# relayboard.net
KiCad netlist of a schematic drawn in EAGLE
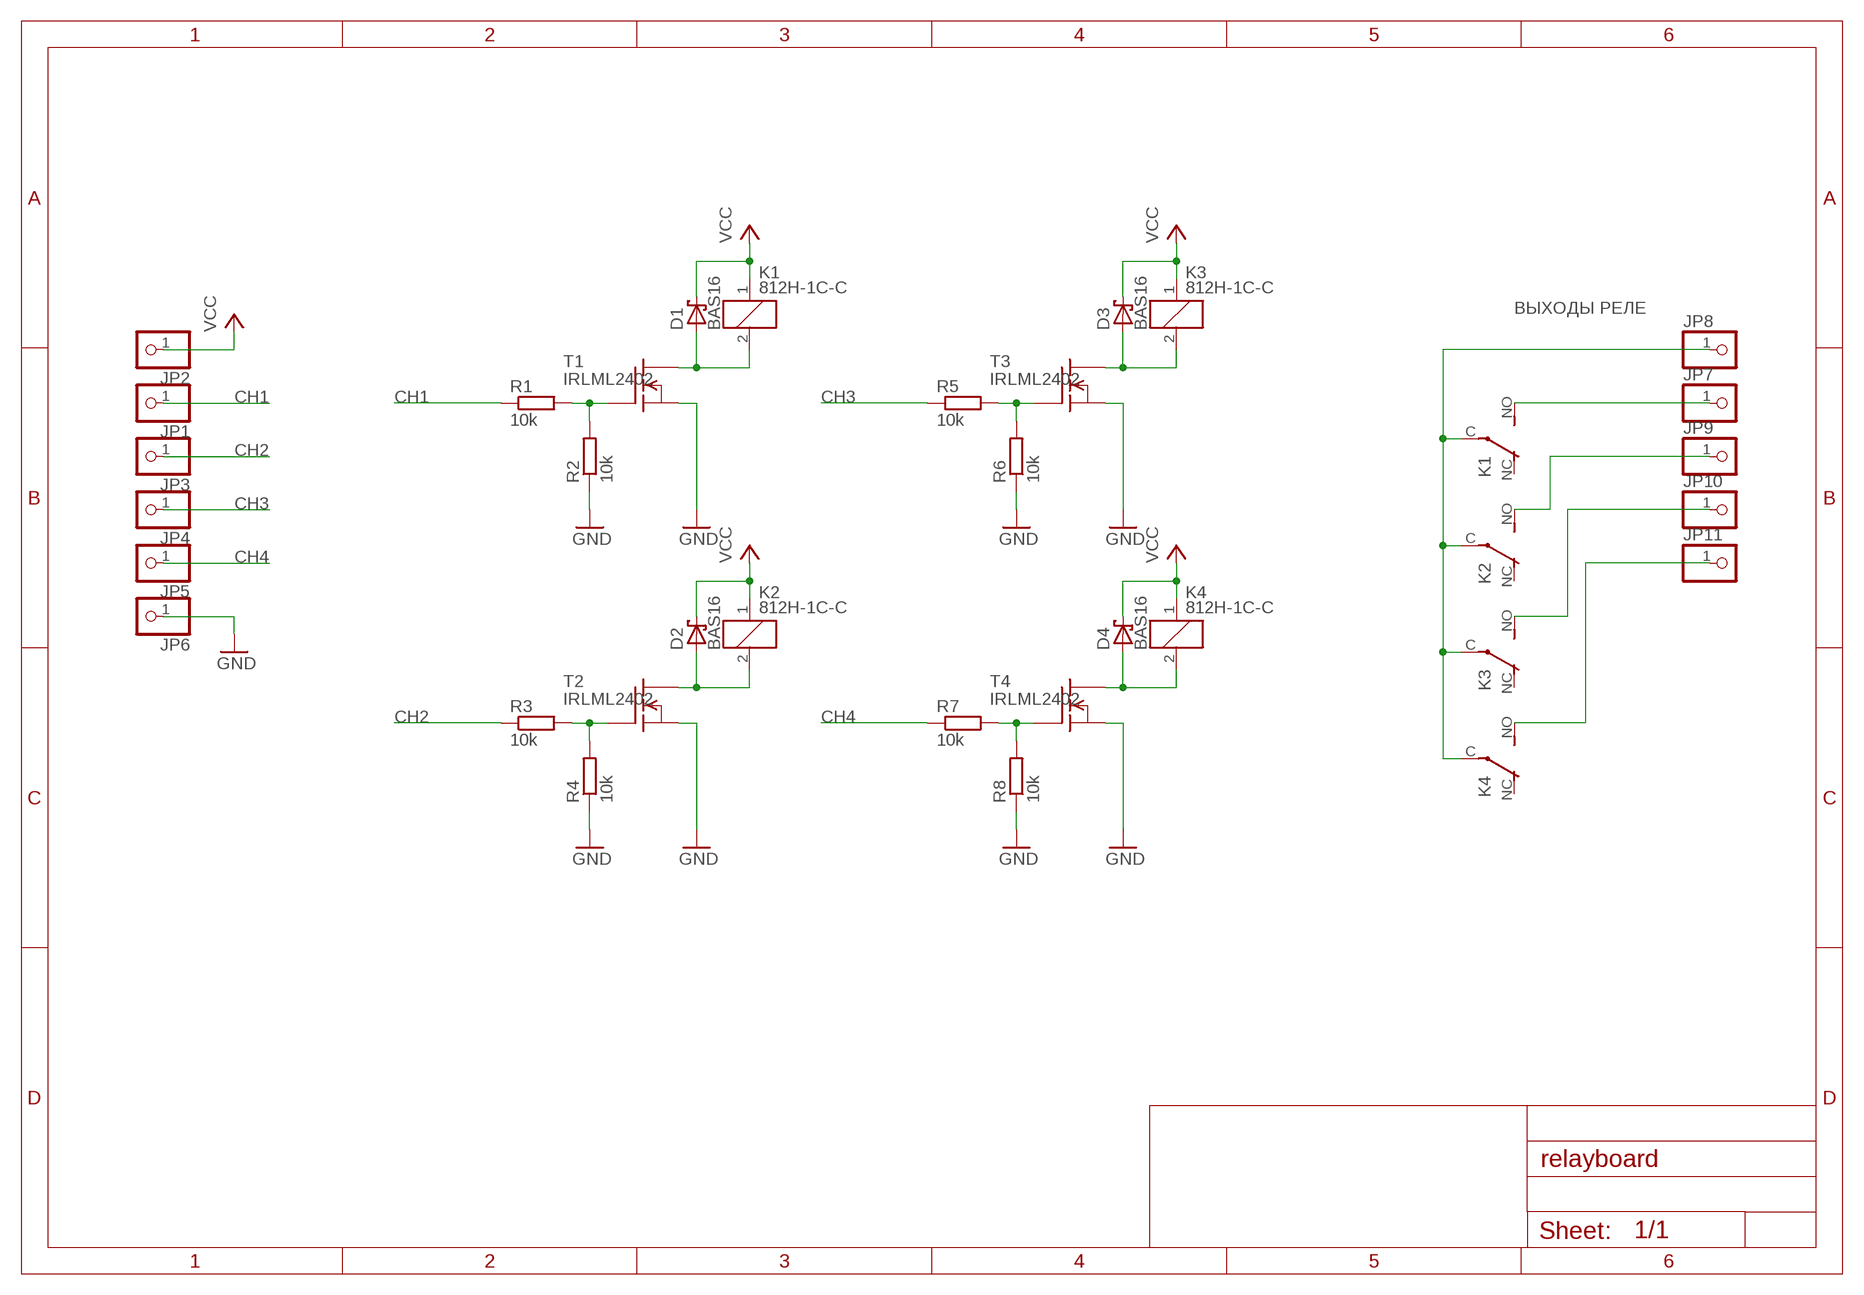
[diagram p0: schematic, sheet 1]

(export (version "E")
  (design (tool "Eeschema 10.0.6"))
  (components
    (comp (ref "D1")
      (value "BAS16")
      (footprint "eagle-import:SOT23")
      (libsource (lib "eagle-import") (part "BAS16"))
    )
    (comp (ref "D2")
      (value "BAS16")
      (footprint "eagle-import:SOT23")
      (libsource (lib "eagle-import") (part "BAS16"))
    )
    (comp (ref "D3")
      (value "BAS16")
      (footprint "eagle-import:SOT23")
      (libsource (lib "eagle-import") (part "BAS16"))
    )
    (comp (ref "D4")
      (value "BAS16")
      (footprint "eagle-import:SOT23")
      (libsource (lib "eagle-import") (part "BAS16"))
    )
    (comp (ref "JP1")
      (value "PINHD-1X1")
      (footprint "eagle-import:1X01")
      (libsource (lib "eagle-import") (part "PINHD-1X1"))
    )
    (comp (ref "JP2")
      (value "PINHD-1X1")
      (footprint "eagle-import:1X01")
      (libsource (lib "eagle-import") (part "PINHD-1X1"))
    )
    (comp (ref "JP3")
      (value "PINHD-1X1")
      (footprint "eagle-import:1X01")
      (libsource (lib "eagle-import") (part "PINHD-1X1"))
    )
    (comp (ref "JP4")
      (value "PINHD-1X1")
      (footprint "eagle-import:1X01")
      (libsource (lib "eagle-import") (part "PINHD-1X1"))
    )
    (comp (ref "JP5")
      (value "PINHD-1X1")
      (footprint "eagle-import:1X01")
      (libsource (lib "eagle-import") (part "PINHD-1X1"))
    )
    (comp (ref "JP6")
      (value "PINHD-1X1")
      (footprint "eagle-import:1X01")
      (libsource (lib "eagle-import") (part "PINHD-1X1"))
    )
    (comp (ref "JP7")
      (value "PINHD-1X1")
      (footprint "eagle-import:1X01")
      (libsource (lib "eagle-import") (part "PINHD-1X1"))
    )
    (comp (ref "JP8")
      (value "PINHD-1X1")
      (footprint "eagle-import:1X01")
      (libsource (lib "eagle-import") (part "PINHD-1X1"))
    )
    (comp (ref "JP9")
      (value "PINHD-1X1")
      (footprint "eagle-import:1X01")
      (libsource (lib "eagle-import") (part "PINHD-1X1"))
    )
    (comp (ref "JP10")
      (value "PINHD-1X1")
      (footprint "eagle-import:1X01")
      (libsource (lib "eagle-import") (part "PINHD-1X1"))
    )
    (comp (ref "JP11")
      (value "PINHD-1X1")
      (footprint "eagle-import:1X01")
      (libsource (lib "eagle-import") (part "PINHD-1X1"))
    )
    (comp (ref "K1")
      (value "812H-1C-C")
      (footprint "eagle-import:CQ1")
      (libsource (lib "eagle-import") (part "812H-1C-C"))
    )
    (comp (ref "K2")
      (value "812H-1C-C")
      (footprint "eagle-import:CQ1")
      (libsource (lib "eagle-import") (part "812H-1C-C"))
    )
    (comp (ref "K3")
      (value "812H-1C-C")
      (footprint "eagle-import:CQ1")
      (libsource (lib "eagle-import") (part "812H-1C-C"))
    )
    (comp (ref "K4")
      (value "812H-1C-C")
      (footprint "eagle-import:CQ1")
      (libsource (lib "eagle-import") (part "812H-1C-C"))
    )
    (comp (ref "R1")
      (value "10k")
      (footprint "eagle-import:M0805")
      (libsource (lib "eagle-import") (part "R-EU_M0805"))
    )
    (comp (ref "R2")
      (value "10k")
      (footprint "eagle-import:R0805")
      (libsource (lib "eagle-import") (part "R-EU_R0805"))
    )
    (comp (ref "R3")
      (value "10k")
      (footprint "eagle-import:R0805")
      (libsource (lib "eagle-import") (part "R-EU_R0805"))
    )
    (comp (ref "R4")
      (value "10k")
      (footprint "eagle-import:R0805")
      (libsource (lib "eagle-import") (part "R-EU_R0805"))
    )
    (comp (ref "R5")
      (value "10k")
      (footprint "eagle-import:R0805")
      (libsource (lib "eagle-import") (part "R-EU_R0805"))
    )
    (comp (ref "R6")
      (value "10k")
      (footprint "eagle-import:R0805")
      (libsource (lib "eagle-import") (part "R-EU_R0805"))
    )
    (comp (ref "R7")
      (value "10k")
      (footprint "eagle-import:R0805")
      (libsource (lib "eagle-import") (part "R-EU_R0805"))
    )
    (comp (ref "R8")
      (value "10k")
      (footprint "eagle-import:R0805")
      (libsource (lib "eagle-import") (part "R-EU_R0805"))
    )
    (comp (ref "T1")
      (value "IRLML2402")
      (footprint "eagle-import:SOT23")
      (libsource (lib "eagle-import") (part "IRLML2402"))
    )
    (comp (ref "T2")
      (value "IRLML2402")
      (footprint "eagle-import:SOT23")
      (libsource (lib "eagle-import") (part "IRLML2402"))
    )
    (comp (ref "T3")
      (value "IRLML2402")
      (footprint "eagle-import:SOT23")
      (libsource (lib "eagle-import") (part "IRLML2402"))
    )
    (comp (ref "T4")
      (value "IRLML2402")
      (footprint "eagle-import:SOT23")
      (libsource (lib "eagle-import") (part "IRLML2402"))
    )
  )
  (nets
    (net (code "1") (name "/CH1") (class "Default")
      (node (ref "JP1") (pin "1") (pinfunction "1_1") (pintype "passive"))
      (node (ref "R1") (pin "1") (pinfunction "1_1") (pintype "passive"))
    )
    (net (code "2") (name "/CH2") (class "Default")
      (node (ref "JP3") (pin "1") (pinfunction "1_1") (pintype "passive"))
      (node (ref "R3") (pin "1") (pinfunction "1_1") (pintype "passive"))
    )
    (net (code "3") (name "/CH3") (class "Default")
      (node (ref "JP4") (pin "1") (pinfunction "1_1") (pintype "passive"))
      (node (ref "R5") (pin "1") (pinfunction "1_1") (pintype "passive"))
    )
    (net (code "4") (name "/CH4") (class "Default")
      (node (ref "JP5") (pin "1") (pinfunction "1_1") (pintype "passive"))
      (node (ref "R7") (pin "1") (pinfunction "1_1") (pintype "passive"))
    )
    (net (code "5") (name "GND") (class "Default")
      (node (ref "JP6") (pin "1") (pinfunction "1_1") (pintype "passive"))
      (node (ref "R2") (pin "1") (pinfunction "1_1") (pintype "passive"))
      (node (ref "R4") (pin "1") (pinfunction "1_1") (pintype "passive"))
      (node (ref "R6") (pin "1") (pinfunction "1_1") (pintype "passive"))
      (node (ref "R8") (pin "1") (pinfunction "1_1") (pintype "passive"))
      (node (ref "T1") (pin "2") (pinfunction "S_2") (pintype "passive"))
      (node (ref "T2") (pin "2") (pinfunction "S_2") (pintype "passive"))
      (node (ref "T3") (pin "2") (pinfunction "S_2") (pintype "passive"))
      (node (ref "T4") (pin "2") (pinfunction "S_2") (pintype "passive"))
    )
    (net (code "6") (name "Net-(D1-A)") (class "Default")
      (node (ref "D1") (pin "1") (pinfunction "A_1") (pintype "passive"))
      (node (ref "K1") (pin "2") (pinfunction "2_2") (pintype "passive"))
      (node (ref "T1") (pin "3") (pinfunction "D_3") (pintype "passive"))
    )
    (net (code "7") (name "Net-(D2-A)") (class "Default")
      (node (ref "D2") (pin "1") (pinfunction "A_1") (pintype "passive"))
      (node (ref "K2") (pin "2") (pinfunction "2_2") (pintype "passive"))
      (node (ref "T2") (pin "3") (pinfunction "D_3") (pintype "passive"))
    )
    (net (code "8") (name "Net-(D3-A)") (class "Default")
      (node (ref "D3") (pin "1") (pinfunction "A_1") (pintype "passive"))
      (node (ref "K3") (pin "2") (pinfunction "2_2") (pintype "passive"))
      (node (ref "T3") (pin "3") (pinfunction "D_3") (pintype "passive"))
    )
    (net (code "9") (name "Net-(D4-A)") (class "Default")
      (node (ref "D4") (pin "1") (pinfunction "A_1") (pintype "passive"))
      (node (ref "K4") (pin "2") (pinfunction "2_2") (pintype "passive"))
      (node (ref "T4") (pin "3") (pinfunction "D_3") (pintype "passive"))
    )
    (net (code "10") (name "Net-(K1B-P)") (class "Default")
      (node (ref "JP8") (pin "1") (pinfunction "1_1") (pintype "passive"))
      (node (ref "K1") (pin "C") (pinfunction "P_C") (pintype "passive"))
      (node (ref "K2") (pin "C") (pinfunction "P_C") (pintype "passive"))
      (node (ref "K3") (pin "C") (pinfunction "P_C") (pintype "passive"))
      (node (ref "K4") (pin "C") (pinfunction "P_C") (pintype "passive"))
    )
    (net (code "11") (name "Net-(K1B-S)") (class "Default")
      (node (ref "JP7") (pin "1") (pinfunction "1_1") (pintype "passive"))
      (node (ref "K1") (pin "NO") (pinfunction "S_NO") (pintype "passive"))
    )
    (net (code "12") (name "Net-(K2B-S)") (class "Default")
      (node (ref "JP9") (pin "1") (pinfunction "1_1") (pintype "passive"))
      (node (ref "K2") (pin "NO") (pinfunction "S_NO") (pintype "passive"))
    )
    (net (code "13") (name "Net-(K3B-S)") (class "Default")
      (node (ref "JP10") (pin "1") (pinfunction "1_1") (pintype "passive"))
      (node (ref "K3") (pin "NO") (pinfunction "S_NO") (pintype "passive"))
    )
    (net (code "14") (name "Net-(K4B-S)") (class "Default")
      (node (ref "JP11") (pin "1") (pinfunction "1_1") (pintype "passive"))
      (node (ref "K4") (pin "NO") (pinfunction "S_NO") (pintype "passive"))
    )
    (net (code "15") (name "Net-(T1-G)") (class "Default")
      (node (ref "R1") (pin "2") (pinfunction "2_2") (pintype "passive"))
      (node (ref "R2") (pin "2") (pinfunction "2_2") (pintype "passive"))
      (node (ref "T1") (pin "1") (pinfunction "G_1") (pintype "passive"))
    )
    (net (code "16") (name "Net-(T2-G)") (class "Default")
      (node (ref "R3") (pin "2") (pinfunction "2_2") (pintype "passive"))
      (node (ref "R4") (pin "2") (pinfunction "2_2") (pintype "passive"))
      (node (ref "T2") (pin "1") (pinfunction "G_1") (pintype "passive"))
    )
    (net (code "17") (name "Net-(T3-G)") (class "Default")
      (node (ref "R5") (pin "2") (pinfunction "2_2") (pintype "passive"))
      (node (ref "R6") (pin "2") (pinfunction "2_2") (pintype "passive"))
      (node (ref "T3") (pin "1") (pinfunction "G_1") (pintype "passive"))
    )
    (net (code "18") (name "Net-(T4-G)") (class "Default")
      (node (ref "R7") (pin "2") (pinfunction "2_2") (pintype "passive"))
      (node (ref "R8") (pin "2") (pinfunction "2_2") (pintype "passive"))
      (node (ref "T4") (pin "1") (pinfunction "G_1") (pintype "passive"))
    )
    (net (code "19") (name "VCC") (class "Default")
      (node (ref "D1") (pin "3") (pinfunction "C_3") (pintype "passive"))
      (node (ref "D2") (pin "3") (pinfunction "C_3") (pintype "passive"))
      (node (ref "D3") (pin "3") (pinfunction "C_3") (pintype "passive"))
      (node (ref "D4") (pin "3") (pinfunction "C_3") (pintype "passive"))
      (node (ref "JP2") (pin "1") (pinfunction "1_1") (pintype "passive"))
      (node (ref "K1") (pin "1") (pinfunction "1_1") (pintype "passive"))
      (node (ref "K2") (pin "1") (pinfunction "1_1") (pintype "passive"))
      (node (ref "K3") (pin "1") (pinfunction "1_1") (pintype "passive"))
      (node (ref "K4") (pin "1") (pinfunction "1_1") (pintype "passive"))
    )
    (net (code "20") (name "unconnected-(K1B-O-PadNC)") (class "Default")
      (node (ref "K1") (pin "NC") (pinfunction "O_NC") (pintype "passive"))
    )
    (net (code "21") (name "unconnected-(K2B-O-PadNC)") (class "Default")
      (node (ref "K2") (pin "NC") (pinfunction "O_NC") (pintype "passive"))
    )
    (net (code "22") (name "unconnected-(K3B-O-PadNC)") (class "Default")
      (node (ref "K3") (pin "NC") (pinfunction "O_NC") (pintype "passive"))
    )
    (net (code "23") (name "unconnected-(K4B-O-PadNC)") (class "Default")
      (node (ref "K4") (pin "NC") (pinfunction "O_NC") (pintype "passive"))
    )
  )
)
